# rp2350a.net
KiCad netlist of a schematic drawn in Altium Designer
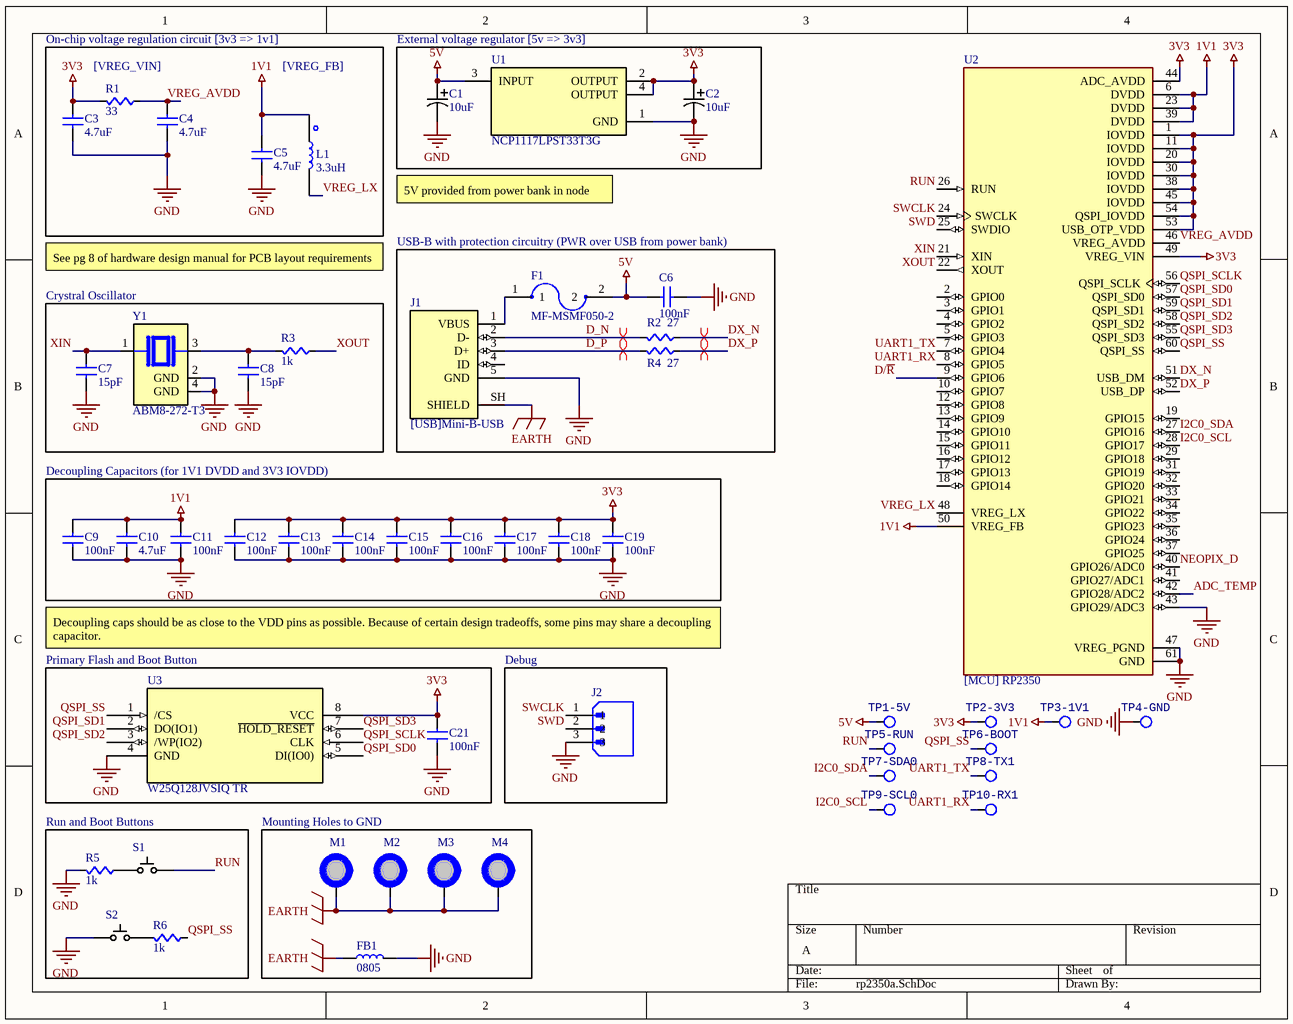
[diagram p0: rp2350a.SchDoc]

(export (version "E")
  (design (tool "Eeschema 10.0.6"))
  (components
    (comp (ref "C1")
      (value "10uF")
      (footprint "RADIAL_CAN_CAP_4_X_5.8_SMD")
      (description "10uF electrolytic cap, radial can, SMD")
      (fields
        (field (name "MANUFACTURER_PART_NUMBER") "EEE-FK1E100R")
        (field (name "COPYRIGHT") "Copyright (C) 2025 Ultra Librarian. All rights reserved.")
      )
      (libsource (lib "Alexandria") (part "EEE-FK1E100R"))
    )
    (comp (ref "C2")
      (value "10uF")
      (footprint "RADIAL_CAN_CAP_4_X_5.8_SMD")
      (description "10uF electrolytic cap, radial can, SMD")
      (fields
        (field (name "MANUFACTURER_PART_NUMBER") "EEE-FK1E100R")
        (field (name "COPYRIGHT") "Copyright (C) 2025 Ultra Librarian. All rights reserved.")
      )
      (libsource (lib "Alexandria") (part "EEE-FK1E100R"))
    )
    (comp (ref "C3")
      (value "4.7uF")
      (footprint "CAPC0603")
      (fields (field (name "Comment") "Cap"))
      (libsource (lib "Passives") (part "Cap"))
    )
    (comp (ref "C4")
      (value "4.7uF")
      (footprint "CAPC0603")
      (fields (field (name "Comment") "Cap"))
      (libsource (lib "Passives") (part "Cap"))
    )
    (comp (ref "C5")
      (value "4.7uF")
      (footprint "CAPC0603")
      (fields (field (name "Comment") "Cap"))
      (libsource (lib "Passives") (part "Cap"))
    )
    (comp (ref "C6")
      (value "100nF")
      (footprint "CAPC0603")
      (fields (field (name "Comment") "Cap"))
      (libsource (lib "Passives") (part "Cap"))
    )
    (comp (ref "C7")
      (value "15pF")
      (footprint "CAPC0603")
      (fields (field (name "Comment") "Cap"))
      (libsource (lib "Passives") (part "Cap"))
    )
    (comp (ref "C8")
      (value "15pF")
      (footprint "CAPC0603")
      (fields (field (name "Comment") "Cap"))
      (libsource (lib "Passives") (part "Cap"))
    )
    (comp (ref "C9")
      (value "100nF")
      (footprint "CAPC0603")
      (fields (field (name "Comment") "Cap"))
      (libsource (lib "Passives") (part "Cap"))
    )
    (comp (ref "C10")
      (value "4.7uF")
      (footprint "CAPC0603")
      (fields (field (name "Comment") "Cap"))
      (libsource (lib "Passives") (part "Cap"))
    )
    (comp (ref "C11")
      (value "100nF")
      (footprint "CAPC0603")
      (fields (field (name "Comment") "Cap"))
      (libsource (lib "Passives") (part "Cap"))
    )
    (comp (ref "C12")
      (value "100nF")
      (footprint "CAPC0603")
      (fields (field (name "Comment") "Cap"))
      (libsource (lib "Passives") (part "Cap"))
    )
    (comp (ref "C13")
      (value "100nF")
      (footprint "CAPC0603")
      (fields (field (name "Comment") "Cap"))
      (libsource (lib "Passives") (part "Cap"))
    )
    (comp (ref "C14")
      (value "100nF")
      (footprint "CAPC0603")
      (fields (field (name "Comment") "Cap"))
      (libsource (lib "Passives") (part "Cap"))
    )
    (comp (ref "C15")
      (value "100nF")
      (footprint "CAPC0603")
      (fields (field (name "Comment") "Cap"))
      (libsource (lib "Passives") (part "Cap"))
    )
    (comp (ref "C16")
      (value "100nF")
      (footprint "CAPC0603")
      (fields (field (name "Comment") "Cap"))
      (libsource (lib "Passives") (part "Cap"))
    )
    (comp (ref "C17")
      (value "100nF")
      (footprint "CAPC0603")
      (fields (field (name "Comment") "Cap"))
      (libsource (lib "Passives") (part "Cap"))
    )
    (comp (ref "C18")
      (value "100nF")
      (footprint "CAPC0603")
      (fields (field (name "Comment") "Cap"))
      (libsource (lib "Passives") (part "Cap"))
    )
    (comp (ref "C19")
      (value "100nF")
      (footprint "CAPC0603")
      (fields (field (name "Comment") "Cap"))
      (libsource (lib "Passives") (part "Cap"))
    )
    (comp (ref "C21")
      (value "100nF")
      (footprint "CAPC0603")
      (fields (field (name "Comment") "Cap"))
      (libsource (lib "Passives") (part "Cap"))
    )
    (comp (ref "F1")
      (value "MF-MSMF050-2")
      (footprint "FUSM4632X85")
      (description "[Fuse] Polymeric PTC Resettable Fuse 15V 500 mA Ih Surface Mount 1812 (4532 Metric), Concave")
      (fields (field (name "MF") "Bourns"))
      (libsource (lib "Alexandria") (part "MF-MSMF050-2"))
    )
    (comp (ref "FB1")
      (value "0805")
      (footprint "L0805")
      (description "[Inductor] Ferrite Bead Bourns MH2029-300Y\r\nSMD-FERRITE-BEAD-30R-3A(0805)")
      (fields (field (name "MF") "Bourns") (field (name "MP") "MH2029-300Y"))
      (libsource (lib "Alexandria") (part "MH2029-300Y"))
    )
    (comp (ref "J1")
      (value "[USB]Mini-B-USB")
      (footprint "SAMTEC_MUSB-05-X-B-SM-A-R-K-TR")
      (fields (field (name "MF") "Samtec") (field (name "MP") "MUSB-05-F-B-SM-A-R-K-TR"))
      (libsource (lib "Alexandria") (part "[USB]Mini-B-USB"))
    )
    (comp (ref "J2")
      (value "[Connector] 1x3-header-2.54mm pitch")
      (footprint "1x3-2.54MM-MALE-HEADER")
      (description "1x3 2.54mm header")
      (fields (field (name "MP") "G800W305018EU") (field (name "MF") "FCI Connectors"))
      (libsource (lib "Alexandria") (part "[Connector] 1x3-header-2.54mm pitch"))
    )
    (comp (ref "L1")
      (value "3.3uH")
      (footprint "2016_SMD_Inductor")
      (description "Power Inductors - SMD IND 3.3uH used for RP2350 VREG")
      (fields
        (field (name "MOUSER PART NUMBER") "815-AB201610S3R3101T")
        (field (name "MANUFACTURER_PART_NUMBER") "AOTA-B201610S3R3-101-T")
      )
      (libsource (lib "Alexandria") (part "INDUCTOR 3.3uH"))
    )
    (comp (ref "M1")
      (value "M3 Mount Hole")
      (footprint "3.5MM-MOUNTING-HOLE")
      (description "Place at least 4.5mm from board edge. Plated.")
      (libsource (lib "Alexandria") (part "[Mount] M3 Mount Hole"))
    )
    (comp (ref "M2")
      (value "M3 Mount Hole")
      (footprint "3.5MM-MOUNTING-HOLE")
      (description "Place at least 4.5mm from board edge. Plated.")
      (libsource (lib "Alexandria") (part "[Mount] M3 Mount Hole"))
    )
    (comp (ref "M3")
      (value "M3 Mount Hole")
      (footprint "3.5MM-MOUNTING-HOLE")
      (description "Place at least 4.5mm from board edge. Plated.")
      (libsource (lib "Alexandria") (part "[Mount] M3 Mount Hole"))
    )
    (comp (ref "M4")
      (value "M3 Mount Hole")
      (footprint "3.5MM-MOUNTING-HOLE")
      (description "Place at least 4.5mm from board edge. Plated.")
      (libsource (lib "Alexandria") (part "[Mount] M3 Mount Hole"))
    )
    (comp (ref "R1")
      (value "33")
      (footprint "RES0603")
      (description "SMD, RES0603")
      (fields (field (name "Comment") "Res"))
      (libsource (lib "Passives") (part "Res"))
    )
    (comp (ref "R2")
      (value "27")
      (footprint "RES0603")
      (description "SMD, RES0603")
      (fields (field (name "Comment") "Res"))
      (libsource (lib "Passives") (part "Res"))
    )
    (comp (ref "R3")
      (value "1k")
      (footprint "RES0603")
      (description "SMD, RES0603")
      (fields (field (name "Comment") "Res"))
      (libsource (lib "Passives") (part "Res"))
    )
    (comp (ref "R4")
      (value "27")
      (footprint "RES0603")
      (description "SMD, RES0603")
      (fields (field (name "Comment") "Res"))
      (libsource (lib "Passives") (part "Res"))
    )
    (comp (ref "R5")
      (value "1k")
      (footprint "RES0603")
      (description "SMD, RES0603")
      (fields (field (name "Comment") "Res"))
      (libsource (lib "Passives") (part "Res"))
    )
    (comp (ref "R6")
      (value "1k")
      (footprint "RES0603")
      (description "SMD, RES0603")
      (fields (field (name "Comment") "Res"))
      (libsource (lib "Passives") (part "Res"))
    )
    (comp (ref "S1")
      (value "[SPST] SMD Pushbutton")
      (footprint "[SPST] SMD Pushbutton")
      (description "PTS815SJM250SMTRLFS")
      (libsource (lib "Alexandria") (part "[SPST] SMD Pushbutton"))
    )
    (comp (ref "S2")
      (value "[SPST] SMD Pushbutton")
      (footprint "[SPST] SMD Pushbutton")
      (description "PTS815SJM250SMTRLFS")
      (libsource (lib "Alexandria") (part "[SPST] SMD Pushbutton"))
    )
    (comp (ref "TP1-5V")
      (value "TP")
      (footprint "TPTH-100mil")
      (description "Test Point")
      (libsource (lib "Misc") (part "TP"))
    )
    (comp (ref "TP2-3V3")
      (value "TP")
      (footprint "TPTH-100mil")
      (description "Test Point")
      (libsource (lib "Misc") (part "TP"))
    )
    (comp (ref "TP3-1V1")
      (value "TP")
      (footprint "TPTH-100mil")
      (description "Test Point")
      (libsource (lib "Misc") (part "TP"))
    )
    (comp (ref "TP4-GND")
      (value "TP")
      (footprint "TPTH-100mil")
      (description "Test Point")
      (libsource (lib "Misc") (part "TP"))
    )
    (comp (ref "TP5-RUN")
      (value "TP")
      (footprint "TPTH-100mil")
      (description "Test Point")
      (libsource (lib "Misc") (part "TP"))
    )
    (comp (ref "TP6-BOOT")
      (value "TP")
      (footprint "TPTH-100mil")
      (description "Test Point")
      (libsource (lib "Misc") (part "TP"))
    )
    (comp (ref "TP7-SDA0")
      (value "TP")
      (footprint "TPTH-100mil")
      (description "Test Point")
      (libsource (lib "Misc") (part "TP"))
    )
    (comp (ref "TP8-TX1")
      (value "TP")
      (footprint "TPTH-100mil")
      (description "Test Point")
      (libsource (lib "Misc") (part "TP"))
    )
    (comp (ref "TP9-SCL0")
      (value "TP")
      (footprint "TPTH-100mil")
      (description "Test Point")
      (libsource (lib "Misc") (part "TP"))
    )
    (comp (ref "TP10-RX1")
      (value "TP")
      (footprint "TPTH-100mil")
      (description "Test Point")
      (libsource (lib "Misc") (part "TP"))
    )
    (comp (ref "U1")
      (value "NCP1117LPST33T3G")
      (footprint "SOT230P700X175-4N")
      (description "Linear Voltage Regulator IC Positive Fixed 1 Output 1A SOT-223")
      (fields (field (name "MF") "ON Semiconductor"))
      (libsource (lib "Alexandria") (part "NCP1117LPST33T3G"))
    )
    (comp (ref "U2")
      (value "[MCU] RP2350")
      (footprint "QFN40P700X700X90-61N")
      (description "RP2350A MCU from Raspberry Pi Pico; QFN 60 7x7,")
      (fields (field (name "MF") "Raspberry Pi") (field (name "MP") "SC1509-A4"))
      (libsource (lib "Alexandria") (part "SC1509(13)"))
    )
    (comp (ref "U3")
      (value "W25Q128JVSIQ TR")
      (footprint "SOIC-8-W-208MIL-2")
      (description "IC FLASH 128MBIT SPI/QUAD 8SOIC")
      (fields (field (name "COPYRIGHT") "Copyright (C) 2025 Ultra Librarian. All rights reserved."))
      (libsource (lib "Alexandria") (part "W25Q128JVSIQ TR"))
    )
    (comp (ref "Y1")
      (value "ABM8-272-T3")
      (footprint "XTAL_ABM8-272-T3")
      (description "12 MHz Â±30ppm Crystal 10pF 50 Ohms 4-SMD, No Lead")
      (fields (field (name "MF") "ABRACON"))
      (libsource (lib "Alexandria") (part "ABM8-272-T3"))
    )
  )
  (nets
    (net (code "1") (name "/ADC_TEMP") (class "Default")
      (node (ref "U2") (pin "42") (pinfunction "GPIO28/ADC2_42") (pintype "bidirectional"))
    )
    (net (code "2") (name "/DX_N") (class "Default")
      (node (ref "R2") (pin "2") (pinfunction "B_2") (pintype "passive"))
      (node (ref "U2") (pin "51") (pinfunction "USB_DM_51") (pintype "bidirectional"))
    )
    (net (code "3") (name "/DX_P") (class "Default")
      (node (ref "R4") (pin "2") (pinfunction "B_2") (pintype "passive"))
      (node (ref "U2") (pin "52") (pinfunction "USB_DP_52") (pintype "bidirectional"))
    )
    (net (code "4") (name "/D_N") (class "Default")
      (node (ref "J1") (pin "2") (pinfunction "D-_2") (pintype "bidirectional"))
      (node (ref "R2") (pin "1") (pinfunction "A_1") (pintype "passive"))
    )
    (net (code "5") (name "/D_P") (class "Default")
      (node (ref "J1") (pin "3") (pinfunction "D+_3") (pintype "bidirectional"))
      (node (ref "R4") (pin "1") (pinfunction "A_1") (pintype "passive"))
    )
    (net (code "6") (name "/D{slash}~{R}") (class "Default")
      (node (ref "U2") (pin "9") (pinfunction "GPIO6_9") (pintype "bidirectional"))
    )
    (net (code "7") (name "/I2C0_SCL") (class "Default")
      (node (ref "TP9-SCL0") (pin "1") (pinfunction "1_1") (pintype "passive"))
      (node (ref "U2") (pin "28") (pinfunction "GPIO17_28") (pintype "bidirectional"))
    )
    (net (code "8") (name "/I2C0_SDA") (class "Default")
      (node (ref "TP7-SDA0") (pin "1") (pinfunction "1_1") (pintype "passive"))
      (node (ref "U2") (pin "27") (pinfunction "GPIO16_27") (pintype "bidirectional"))
    )
    (net (code "9") (name "/NEOPIX_D") (class "Default")
      (node (ref "U2") (pin "40") (pinfunction "GPIO26/ADC0_40") (pintype "bidirectional"))
    )
    (net (code "10") (name "/QSPI_SCLK") (class "Default")
      (node (ref "U2") (pin "56") (pinfunction "QSPI_SCLK_56") (pintype "bidirectional"))
      (node (ref "U3") (pin "6") (pinfunction "CLK_6") (pintype "input"))
    )
    (net (code "11") (name "/QSPI_SD0") (class "Default")
      (node (ref "U2") (pin "57") (pinfunction "QSPI_SD0_57") (pintype "bidirectional"))
      (node (ref "U3") (pin "5") (pinfunction "DI(IO0)_5") (pintype "bidirectional"))
    )
    (net (code "12") (name "/QSPI_SD1") (class "Default")
      (node (ref "U2") (pin "59") (pinfunction "QSPI_SD1_59") (pintype "bidirectional"))
      (node (ref "U3") (pin "2") (pinfunction "DO(IO1)_2") (pintype "bidirectional"))
    )
    (net (code "13") (name "/QSPI_SD2") (class "Default")
      (node (ref "U2") (pin "58") (pinfunction "QSPI_SD2_58") (pintype "bidirectional"))
      (node (ref "U3") (pin "3") (pinfunction "/WP(IO2)_3") (pintype "bidirectional"))
    )
    (net (code "14") (name "/QSPI_SD3") (class "Default")
      (node (ref "U2") (pin "55") (pinfunction "QSPI_SD3_55") (pintype "bidirectional"))
      (node (ref "U3") (pin "7") (pinfunction "~{HOLD_RESET}_7") (pintype "bidirectional"))
    )
    (net (code "15") (name "/QSPI_SS") (class "Default")
      (node (ref "R6") (pin "2") (pinfunction "B_2") (pintype "passive"))
      (node (ref "TP6-BOOT") (pin "1") (pinfunction "1_1") (pintype "passive"))
      (node (ref "U2") (pin "60") (pinfunction "QSPI_SS_60") (pintype "bidirectional"))
      (node (ref "U3") (pin "1") (pinfunction "/CS_1") (pintype "input"))
    )
    (net (code "16") (name "/RUN") (class "Default")
      (node (ref "S1") (pin "2") (pintype "power_in"))
      (node (ref "TP5-RUN") (pin "1") (pinfunction "1_1") (pintype "passive"))
      (node (ref "U2") (pin "26") (pinfunction "RUN_26") (pintype "input"))
    )
    (net (code "17") (name "/SWCLK") (class "Default")
      (node (ref "J2") (pin "1") (pinfunction "1_1") (pintype "passive"))
      (node (ref "U2") (pin "24") (pinfunction "SWCLK_24") (pintype "input"))
    )
    (net (code "18") (name "/SWD") (class "Default")
      (node (ref "J2") (pin "2") (pinfunction "2_2") (pintype "passive"))
      (node (ref "U2") (pin "25") (pinfunction "SWDIO_25") (pintype "bidirectional"))
    )
    (net (code "19") (name "/UART1_RX") (class "Default")
      (node (ref "TP10-RX1") (pin "1") (pinfunction "1_1") (pintype "passive"))
      (node (ref "U2") (pin "8") (pinfunction "GPIO5_8") (pintype "bidirectional"))
    )
    (net (code "20") (name "/UART1_TX") (class "Default")
      (node (ref "TP8-TX1") (pin "1") (pinfunction "1_1") (pintype "passive"))
      (node (ref "U2") (pin "7") (pinfunction "GPIO4_7") (pintype "bidirectional"))
    )
    (net (code "21") (name "/VREG_AVDD") (class "Default")
      (node (ref "C4") (pin "1") (pinfunction "A_1") (pintype "passive"))
      (node (ref "R1") (pin "2") (pinfunction "B_2") (pintype "passive"))
      (node (ref "U2") (pin "46") (pinfunction "VREG_AVDD_46") (pintype "power_in"))
    )
    (net (code "22") (name "/VREG_LX") (class "Default")
      (node (ref "L1") (pin "2") (pinfunction "2_2") (pintype "passive"))
      (node (ref "U2") (pin "48") (pinfunction "VREG_LX_48") (pintype "passive"))
    )
    (net (code "23") (name "/XIN") (class "Default")
      (node (ref "C7") (pin "1") (pinfunction "A_1") (pintype "passive"))
      (node (ref "U2") (pin "21") (pinfunction "XIN_21") (pintype "input"))
      (node (ref "Y1") (pin "1") (pinfunction "1_1") (pintype "passive"))
    )
    (net (code "24") (name "/XOUT") (class "Default")
      (node (ref "R3") (pin "2") (pinfunction "B_2") (pintype "passive"))
      (node (ref "U2") (pin "22") (pinfunction "XOUT_22") (pintype "output"))
    )
    (net (code "25") (name "1V1") (class "Default")
      (node (ref "C10") (pin "1") (pinfunction "A_1") (pintype "passive"))
      (node (ref "C11") (pin "1") (pinfunction "A_1") (pintype "passive"))
      (node (ref "C5") (pin "1") (pinfunction "A_1") (pintype "passive"))
      (node (ref "C9") (pin "1") (pinfunction "A_1") (pintype "passive"))
      (node (ref "L1") (pin "1") (pinfunction "1_1") (pintype "passive"))
      (node (ref "TP3-1V1") (pin "1") (pinfunction "1_1") (pintype "passive"))
      (node (ref "U2") (pin "23") (pinfunction "DVDD_23") (pintype "power_in"))
      (node (ref "U2") (pin "39") (pinfunction "DVDD_39") (pintype "power_in"))
      (node (ref "U2") (pin "50") (pinfunction "VREG_FB_50") (pintype "passive"))
      (node (ref "U2") (pin "6") (pinfunction "DVDD_6") (pintype "power_in"))
    )
    (net (code "26") (name "3V3") (class "Default")
      (node (ref "C12") (pin "1") (pinfunction "A_1") (pintype "passive"))
      (node (ref "C13") (pin "1") (pinfunction "A_1") (pintype "passive"))
      (node (ref "C14") (pin "1") (pinfunction "A_1") (pintype "passive"))
      (node (ref "C15") (pin "1") (pinfunction "A_1") (pintype "passive"))
      (node (ref "C16") (pin "1") (pinfunction "A_1") (pintype "passive"))
      (node (ref "C17") (pin "1") (pinfunction "A_1") (pintype "passive"))
      (node (ref "C18") (pin "1") (pinfunction "A_1") (pintype "passive"))
      (node (ref "C19") (pin "1") (pinfunction "A_1") (pintype "passive"))
      (node (ref "C2") (pin "1") (pinfunction "1_1") (pintype "passive"))
      (node (ref "C21") (pin "1") (pinfunction "A_1") (pintype "passive"))
      (node (ref "C3") (pin "1") (pinfunction "A_1") (pintype "passive"))
      (node (ref "R1") (pin "1") (pinfunction "A_1") (pintype "passive"))
      (node (ref "TP2-3V3") (pin "1") (pinfunction "1_1") (pintype "passive"))
      (node (ref "U1") (pin "2") (pinfunction "OUTPUT_2") (pintype "passive"))
      (node (ref "U1") (pin "4") (pinfunction "OUTPUT_4") (pintype "passive"))
      (node (ref "U2") (pin "1") (pinfunction "IOVDD_1") (pintype "power_in"))
      (node (ref "U2") (pin "11") (pinfunction "IOVDD_11") (pintype "power_in"))
      (node (ref "U2") (pin "20") (pinfunction "IOVDD_20") (pintype "power_in"))
      (node (ref "U2") (pin "30") (pinfunction "IOVDD_30") (pintype "power_in"))
      (node (ref "U2") (pin "38") (pinfunction "IOVDD_38") (pintype "power_in"))
      (node (ref "U2") (pin "44") (pinfunction "ADC_AVDD_44") (pintype "power_in"))
      (node (ref "U2") (pin "45") (pinfunction "IOVDD_45") (pintype "power_in"))
      (node (ref "U2") (pin "49") (pinfunction "VREG_VIN_49") (pintype "power_in"))
      (node (ref "U2") (pin "53") (pinfunction "USB_OTP_VDD_53") (pintype "power_in"))
      (node (ref "U2") (pin "54") (pinfunction "QSPI_IOVDD_54") (pintype "power_in"))
      (node (ref "U3") (pin "8") (pinfunction "VCC_8") (pintype "power_in"))
    )
    (net (code "27") (name "5V") (class "Default")
      (node (ref "C1") (pin "1") (pinfunction "1_1") (pintype "passive"))
      (node (ref "C6") (pin "2") (pinfunction "B_2") (pintype "passive"))
      (node (ref "F1") (pin "2") (pinfunction "2_2") (pintype "passive"))
      (node (ref "TP1-5V") (pin "1") (pinfunction "1_1") (pintype "passive"))
      (node (ref "U1") (pin "3") (pinfunction "INPUT_3") (pintype "passive"))
    )
    (net (code "28") (name "EARTH") (class "Default")
      (node (ref "FB1") (pin "1") (pinfunction "1_1") (pintype "passive"))
      (node (ref "J1") (pin "SH") (pinfunction "SHIELD_SH") (pintype "passive"))
      (node (ref "M1") (pin "1") (pintype "power_in"))
      (node (ref "M2") (pin "1") (pintype "power_in"))
      (node (ref "M3") (pin "1") (pintype "power_in"))
      (node (ref "M4") (pin "1") (pintype "power_in"))
    )
    (net (code "29") (name "GND") (class "Default")
      (node (ref "C1") (pin "2") (pinfunction "2_2") (pintype "passive"))
      (node (ref "C10") (pin "2") (pinfunction "B_2") (pintype "passive"))
      (node (ref "C11") (pin "2") (pinfunction "B_2") (pintype "passive"))
      (node (ref "C12") (pin "2") (pinfunction "B_2") (pintype "passive"))
      (node (ref "C13") (pin "2") (pinfunction "B_2") (pintype "passive"))
      (node (ref "C14") (pin "2") (pinfunction "B_2") (pintype "passive"))
      (node (ref "C15") (pin "2") (pinfunction "B_2") (pintype "passive"))
      (node (ref "C16") (pin "2") (pinfunction "B_2") (pintype "passive"))
      (node (ref "C17") (pin "2") (pinfunction "B_2") (pintype "passive"))
      (node (ref "C18") (pin "2") (pinfunction "B_2") (pintype "passive"))
      (node (ref "C19") (pin "2") (pinfunction "B_2") (pintype "passive"))
      (node (ref "C2") (pin "2") (pinfunction "2_2") (pintype "passive"))
      (node (ref "C21") (pin "2") (pinfunction "B_2") (pintype "passive"))
      (node (ref "C3") (pin "2") (pinfunction "B_2") (pintype "passive"))
      (node (ref "C4") (pin "2") (pinfunction "B_2") (pintype "passive"))
      (node (ref "C5") (pin "2") (pinfunction "B_2") (pintype "passive"))
      (node (ref "C6") (pin "1") (pinfunction "A_1") (pintype "passive"))
      (node (ref "C7") (pin "2") (pinfunction "B_2") (pintype "passive"))
      (node (ref "C8") (pin "2") (pinfunction "B_2") (pintype "passive"))
      (node (ref "C9") (pin "2") (pinfunction "B_2") (pintype "passive"))
      (node (ref "FB1") (pin "2") (pinfunction "2_2") (pintype "passive"))
      (node (ref "J1") (pin "5") (pinfunction "GND_5") (pintype "power_in"))
      (node (ref "J2") (pin "3") (pinfunction "3_3") (pintype "passive"))
      (node (ref "R5") (pin "1") (pinfunction "A_1") (pintype "passive"))
      (node (ref "S2") (pin "1") (pintype "power_in"))
      (node (ref "TP4-GND") (pin "1") (pinfunction "1_1") (pintype "passive"))
      (node (ref "U1") (pin "1") (pinfunction "GND_1") (pintype "power_in"))
      (node (ref "U2") (pin "43") (pinfunction "GPIO29/ADC3_43") (pintype "bidirectional"))
      (node (ref "U2") (pin "47") (pinfunction "VREG_PGND_47") (pintype "power_in"))
      (node (ref "U2") (pin "61") (pinfunction "GND_61") (pintype "power_in"))
      (node (ref "U3") (pin "4") (pinfunction "GND_4") (pintype "power_in"))
      (node (ref "Y1") (pin "2") (pinfunction "GND_2") (pintype "power_in"))
      (node (ref "Y1") (pin "4") (pinfunction "GND_4") (pintype "power_in"))
    )
    (net (code "30") (name "Net-(C8-A)") (class "Default")
      (node (ref "C8") (pin "1") (pinfunction "A_1") (pintype "passive"))
      (node (ref "R3") (pin "1") (pinfunction "A_1") (pintype "passive"))
      (node (ref "Y1") (pin "3") (pinfunction "3_3") (pintype "passive"))
    )
    (net (code "31") (name "Net-(J1-VBUS)") (class "Default")
      (node (ref "F1") (pin "1") (pinfunction "1_1") (pintype "passive"))
      (node (ref "J1") (pin "1") (pinfunction "VBUS_1") (pintype "power_in"))
    )
    (net (code "32") (name "Net-(R5-B)") (class "Default")
      (node (ref "R5") (pin "2") (pinfunction "B_2") (pintype "passive"))
      (node (ref "S1") (pin "1") (pintype "power_in"))
    )
    (net (code "33") (name "Net-(R6-A)") (class "Default")
      (node (ref "R6") (pin "1") (pinfunction "A_1") (pintype "passive"))
      (node (ref "S2") (pin "2") (pintype "power_in"))
    )
    (net (code "34") (name "unconnected-(J1-ID-Pad4)") (class "Default")
      (node (ref "J1") (pin "4") (pinfunction "ID_4") (pintype "bidirectional"))
    )
    (net (code "35") (name "unconnected-(U2-GPIO0-Pad2)") (class "Default")
      (node (ref "U2") (pin "2") (pinfunction "GPIO0_2") (pintype "bidirectional"))
    )
    (net (code "36") (name "unconnected-(U2-GPIO1-Pad3)") (class "Default")
      (node (ref "U2") (pin "3") (pinfunction "GPIO1_3") (pintype "bidirectional"))
    )
    (net (code "37") (name "unconnected-(U2-GPIO2-Pad4)") (class "Default")
      (node (ref "U2") (pin "4") (pinfunction "GPIO2_4") (pintype "bidirectional"))
    )
    (net (code "38") (name "unconnected-(U2-GPIO3-Pad5)") (class "Default")
      (node (ref "U2") (pin "5") (pinfunction "GPIO3_5") (pintype "bidirectional"))
    )
    (net (code "39") (name "unconnected-(U2-GPIO7-Pad10)") (class "Default")
      (node (ref "U2") (pin "10") (pinfunction "GPIO7_10") (pintype "bidirectional"))
    )
    (net (code "40") (name "unconnected-(U2-GPIO8-Pad12)") (class "Default")
      (node (ref "U2") (pin "12") (pinfunction "GPIO8_12") (pintype "bidirectional"))
    )
    (net (code "41") (name "unconnected-(U2-GPIO9-Pad13)") (class "Default")
      (node (ref "U2") (pin "13") (pinfunction "GPIO9_13") (pintype "bidirectional"))
    )
    (net (code "42") (name "unconnected-(U2-GPIO10-Pad14)") (class "Default")
      (node (ref "U2") (pin "14") (pinfunction "GPIO10_14") (pintype "bidirectional"))
    )
    (net (code "43") (name "unconnected-(U2-GPIO11-Pad15)") (class "Default")
      (node (ref "U2") (pin "15") (pinfunction "GPIO11_15") (pintype "bidirectional"))
    )
    (net (code "44") (name "unconnected-(U2-GPIO12-Pad16)") (class "Default")
      (node (ref "U2") (pin "16") (pinfunction "GPIO12_16") (pintype "bidirectional"))
    )
    (net (code "45") (name "unconnected-(U2-GPIO13-Pad17)") (class "Default")
      (node (ref "U2") (pin "17") (pinfunction "GPIO13_17") (pintype "bidirectional"))
    )
    (net (code "46") (name "unconnected-(U2-GPIO14-Pad18)") (class "Default")
      (node (ref "U2") (pin "18") (pinfunction "GPIO14_18") (pintype "bidirectional"))
    )
    (net (code "47") (name "unconnected-(U2-GPIO15-Pad19)") (class "Default")
      (node (ref "U2") (pin "19") (pinfunction "GPIO15_19") (pintype "bidirectional"))
    )
    (net (code "48") (name "unconnected-(U2-GPIO18-Pad29)") (class "Default")
      (node (ref "U2") (pin "29") (pinfunction "GPIO18_29") (pintype "bidirectional"))
    )
    (net (code "49") (name "unconnected-(U2-GPIO19-Pad31)") (class "Default")
      (node (ref "U2") (pin "31") (pinfunction "GPIO19_31") (pintype "bidirectional"))
    )
    (net (code "50") (name "unconnected-(U2-GPIO20-Pad32)") (class "Default")
      (node (ref "U2") (pin "32") (pinfunction "GPIO20_32") (pintype "bidirectional"))
    )
    (net (code "51") (name "unconnected-(U2-GPIO21-Pad33)") (class "Default")
      (node (ref "U2") (pin "33") (pinfunction "GPIO21_33") (pintype "bidirectional"))
    )
    (net (code "52") (name "unconnected-(U2-GPIO22-Pad34)") (class "Default")
      (node (ref "U2") (pin "34") (pinfunction "GPIO22_34") (pintype "bidirectional"))
    )
    (net (code "53") (name "unconnected-(U2-GPIO23-Pad35)") (class "Default")
      (node (ref "U2") (pin "35") (pinfunction "GPIO23_35") (pintype "bidirectional"))
    )
    (net (code "54") (name "unconnected-(U2-GPIO24-Pad36)") (class "Default")
      (node (ref "U2") (pin "36") (pinfunction "GPIO24_36") (pintype "bidirectional"))
    )
    (net (code "55") (name "unconnected-(U2-GPIO25-Pad37)") (class "Default")
      (node (ref "U2") (pin "37") (pinfunction "GPIO25_37") (pintype "bidirectional"))
    )
    (net (code "56") (name "unconnected-(U2-GPIO27{slash}ADC1-Pad41)") (class "Default")
      (node (ref "U2") (pin "41") (pinfunction "GPIO27/ADC1_41") (pintype "bidirectional"))
    )
  )
)
